# SPI_Flash.net
KiCad netlist of a schematic drawn in Altium Designer
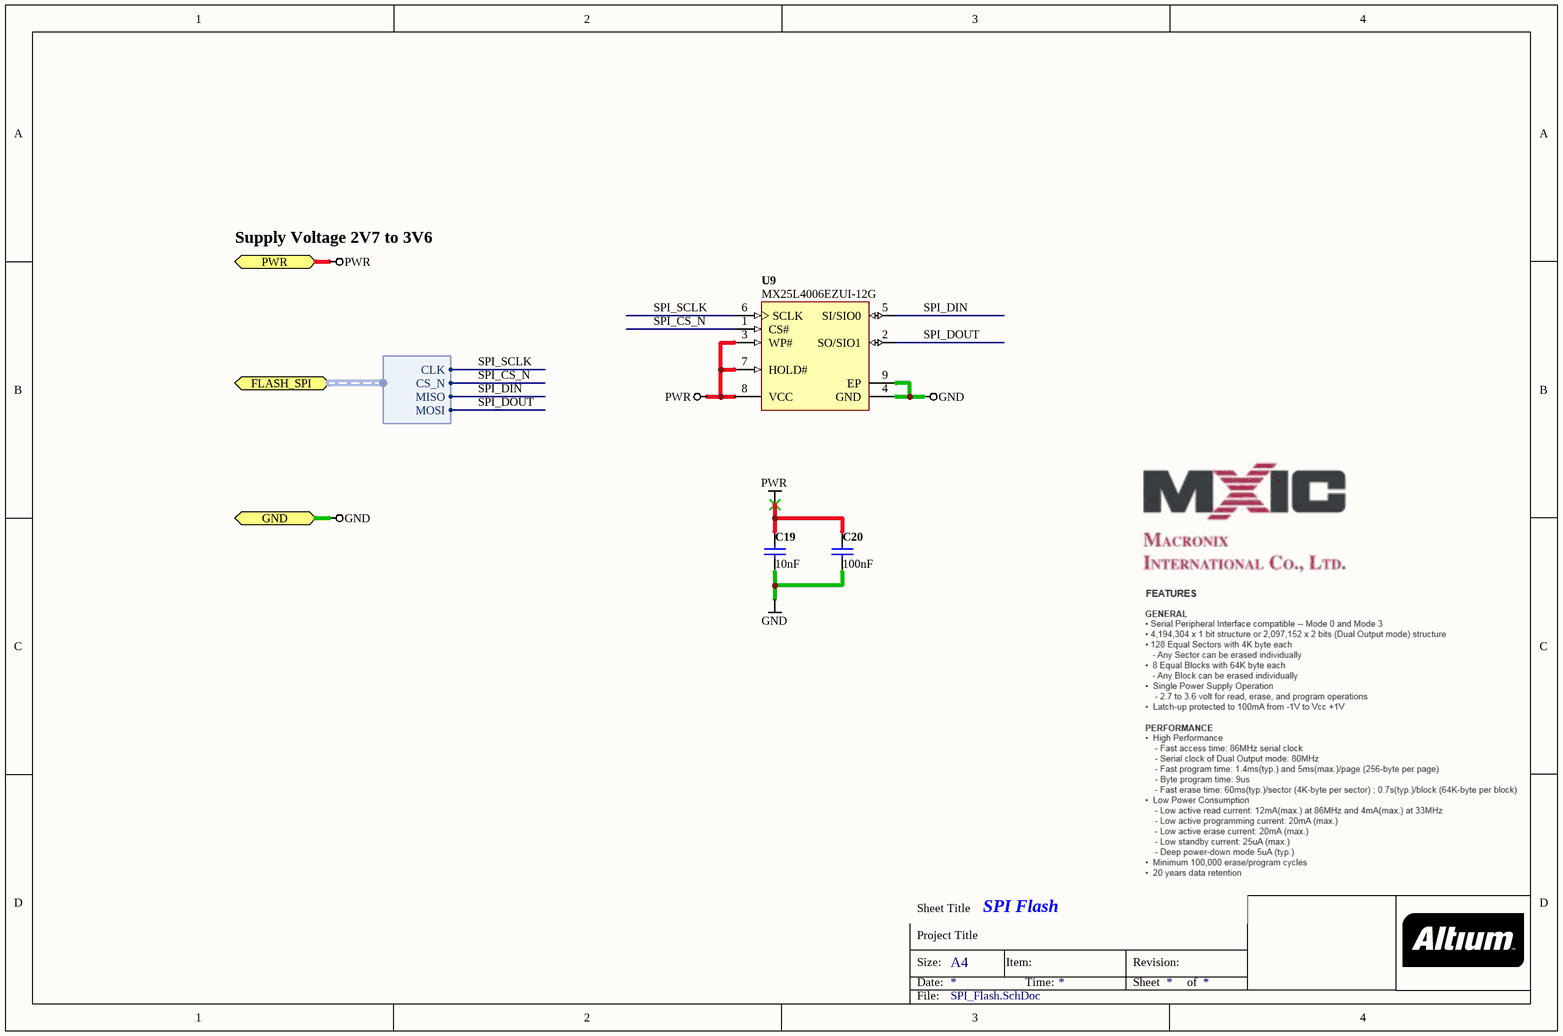
[diagram p0: SPI_Flash.SchDoc]

(export (version "E")
  (design (tool "Eeschema 10.0.6"))
  (components
    (comp (ref "C19")
      (value "10nF")
      (footprint "CAPC0402(1005)60_N")
      (description "CAP 10nF 6.3V ?0% 0402 (1005 Metric) Thickness 0.6mm SMD")
      (fields (field (name "TOLERANCE") "?0%") (field (name "Comment") "CAP 10nF 6.3V 0402(1005)"))
      (libsource (lib "Altium Content Vault") (part "CMP-1034-01869-1"))
    )
    (comp (ref "C20")
      (value "100nF")
      (footprint "CAPC0402(1005)60_N")
      (description "CAP 100nF 6.3V ?0% 0402 (1005 Metric) Thickness 0.6mm SMD")
      (fields (field (name "TOLERANCE") "?0%") (field (name "Comment") "CAP 100nF 6.3V 0402(1005)"))
      (libsource (lib "Altium Content Vault") (part "CMP-1034-02062-1"))
    )
    (comp (ref "U9")
      (value "MX25L4006EZUI-12G")
      (footprint "MXIC-USON-8_V")
      (description "4 M-Bit [x1 / x2] CMOS Serial Flash, 86 MHz, -0.7 to 3.6 V, -40 to 85 degC, Body 2 x 3 x 0.6 mm")
      (fields (field (name "MANUFACTURER") "Macronix"))
      (libsource (lib "Altium Content Vault") (part "MXIC-MX25L4006EZUI-12G-USON-8"))
    )
  )
  (nets
    (net (code "2") (name "/SPI_CS_N") (class "Default")
      (node (ref "U9") (pin "1") (pinfunction "CS#_1") (pintype "input"))
    )
    (net (code "3") (name "/SPI_DIN") (class "Default")
      (node (ref "U9") (pin "5") (pinfunction "SI/SIO0_5") (pintype "bidirectional"))
    )
    (net (code "4") (name "/SPI_DOUT") (class "Default")
      (node (ref "U9") (pin "2") (pinfunction "SO/SIO1_2") (pintype "bidirectional"))
    )
    (net (code "5") (name "/SPI_SCLK") (class "Default")
      (node (ref "U9") (pin "6") (pinfunction "SCLK_6") (pintype "input"))
    )
    (net (code "7") (name "GND") (class "Default")
      (node (ref "C19") (pin "2") (pinfunction "2_2") (pintype "passive"))
      (node (ref "C20") (pin "1") (pinfunction "1_1") (pintype "passive"))
      (node (ref "U9") (pin "4") (pinfunction "GND_4") (pintype "power_in"))
      (node (ref "U9") (pin "9") (pinfunction "EP_9") (pintype "passive"))
    )
    (net (code "8") (name "PWR") (class "Default")
      (node (ref "C19") (pin "1") (pinfunction "1_1") (pintype "passive"))
      (node (ref "C20") (pin "2") (pinfunction "2_2") (pintype "passive"))
      (node (ref "U9") (pin "3") (pinfunction "WP#_3") (pintype "input"))
      (node (ref "U9") (pin "7") (pinfunction "HOLD#_7") (pintype "input"))
      (node (ref "U9") (pin "8") (pinfunction "VCC_8") (pintype "power_in"))
    )
  )
)
